# RF_Amplifier.net
KiCad netlist of a schematic drawn in Altium Designer
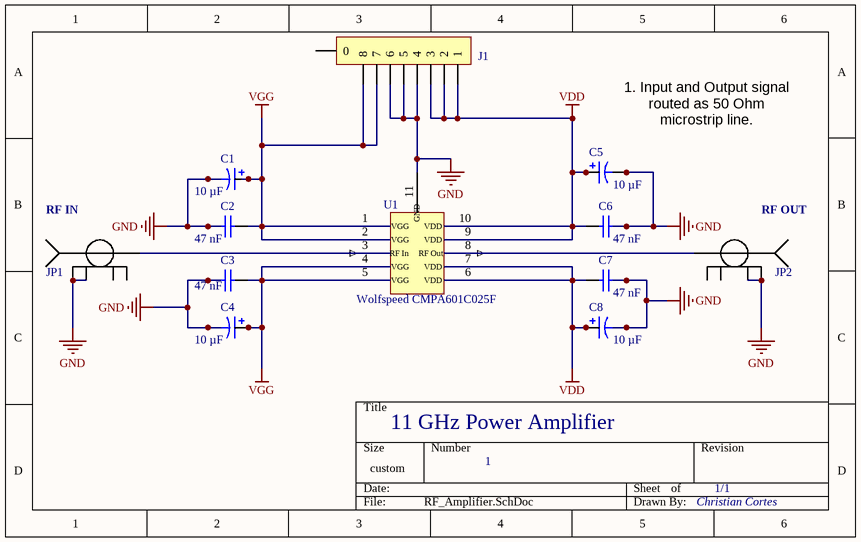
[diagram p0: RF_Amplifier.SchDoc]

(export (version "E")
  (design (tool "Eeschema 10.0.6"))
  (components
    (comp (ref "C1")
      (value "Panasonic 10SVP10M")
      (footprint "PCB-11675369-2")
      (description "CAP ALUM 10UF 10V 20% SMD")
      (fields (field (name "CAPACITANCE") "10 µF") (field (name "MANUFACTURER PART NUMBER") "10SVP10M"))
      (libsource (lib "") (part "SYM-11675369-1_1"))
    )
    (comp (ref "C2")
      (value "AVX Interconnect / Elco 12061C473KAT2A")
      (footprint "CAPC3216X94X50ML20T25")
      (description "CAP CER 0.047UF 100V X7R 1206")
      (fields (field (name "CAPACITANCE") "47 nF") (field (name "MANUFACTURER PART NUMBER") "12061C473KAT2A"))
      (libsource (lib "My Personal Space") (part "CAP-2"))
    )
    (comp (ref "C3")
      (value "AVX Interconnect / Elco 12061C473KAT2A")
      (footprint "CAPC3216X94X50ML20T25")
      (description "CAP CER 0.047UF 100V X7R 1206")
      (fields (field (name "CAPACITANCE") "47 nF") (field (name "MANUFACTURER PART NUMBER") "12061C473KAT2A"))
      (libsource (lib "My Personal Space") (part "CAP-2"))
    )
    (comp (ref "C4")
      (value "Panasonic 10SVP10M")
      (footprint "PCB-11675369-2")
      (description "CAP ALUM 10UF 10V 20% SMD")
      (fields (field (name "CAPACITANCE") "10 µF") (field (name "MANUFACTURER PART NUMBER") "10SVP10M"))
      (libsource (lib "") (part "SYM-11675369-1_1"))
    )
    (comp (ref "C5")
      (value "Panasonic 10SVP10M")
      (footprint "PCB-11675369-2")
      (description "CAP ALUM 10UF 10V 20% SMD")
      (fields (field (name "CAPACITANCE") "10 µF") (field (name "MANUFACTURER PART NUMBER") "10SVP10M"))
      (libsource (lib "My Personal Space") (part "SYM-11675369-1"))
    )
    (comp (ref "C6")
      (value "AVX Interconnect / Elco 12061C473KAT2A")
      (footprint "CAPC3216X94X50ML20T25")
      (description "CAP CER 0.047UF 100V X7R 1206")
      (fields (field (name "CAPACITANCE") "47 nF") (field (name "MANUFACTURER PART NUMBER") "12061C473KAT2A"))
      (libsource (lib "My Personal Space") (part "CAP-2"))
    )
    (comp (ref "C7")
      (value "AVX Interconnect / Elco 12061C473KAT2A")
      (footprint "CAPC3216X94X50ML20T25")
      (description "CAP CER 0.047UF 100V X7R 1206")
      (fields (field (name "CAPACITANCE") "47 nF") (field (name "MANUFACTURER PART NUMBER") "12061C473KAT2A"))
      (libsource (lib "My Personal Space") (part "CAP-2"))
    )
    (comp (ref "C8")
      (value "Panasonic 10SVP10M")
      (footprint "PCB-11675369-2")
      (description "CAP ALUM 10UF 10V 20% SMD")
      (fields (field (name "CAPACITANCE") "10 µF") (field (name "MANUFACTURER PART NUMBER") "10SVP10M"))
      (libsource (lib "My Personal Space") (part "SYM-11675369-1"))
    )
    (comp (ref "J1")
      (value "Molex 53398-0871")
      (footprint "PCB-330964-1")
      (description "Headers & Wire Housings VERTICAL HDR SMT 8P")
      (fields (field (name "MANUFACTURER PART NUMBER") "53398-0871"))
      (libsource (lib "My Personal Space") (part "SYM-330964-1"))
    )
    (comp (ref "JP1")
      (value "Molex 73251-2120")
      (footprint "PCB-gjx2rcg91tbhfhdn1i9r-1")
      (description "Rf Coax Conn, Sma, Jack, 50 Ohm, Pcb")
      (fields (field (name "MANUFACTURER PART NUMBER") "73251-2120"))
      (libsource (lib "My Personal Space") (part "SYM-4dee84f7198e9229-1"))
    )
    (comp (ref "JP2")
      (value "Molex 73251-2120")
      (footprint "PCB-gjx2rcg91tbhfhdn1i9r-1")
      (description "Rf Coax Conn, Sma, Jack, 50 Ohm, Pcb")
      (fields (field (name "MANUFACTURER PART NUMBER") "73251-2120"))
      (libsource (lib "My Personal Space") (part "SYM-4dee84f7198e9229-1"))
    )
    (comp (ref "U1")
      (value "Wolfspeed CMPA601C025F")
      (footprint "Wolfspeed CMPA601C025F-Footprint-1")
      (description "RF Amp Module Single Power Amp 12GHz 28V 11-Pin Case 440213")
      (fields (field (name "MANUFACTURER PART NUMBER") "CMPA601C025F - mod"))
      (libsource (lib "My Personal Space") (part "Wolfspeed CMPA601C025F-Symbol-1"))
    )
  )
  (nets
    (net (code "1") (name "GND") (class "Default")
      (node (ref "C1") (pin "2") (pinfunction "2_2") (pintype "passive"))
      (node (ref "C2") (pin "1") (pinfunction "1_1") (pintype "passive"))
      (node (ref "C3") (pin "1") (pinfunction "1_1") (pintype "passive"))
      (node (ref "C4") (pin "2") (pinfunction "2_2") (pintype "passive"))
      (node (ref "C5") (pin "2") (pinfunction "2_2") (pintype "passive"))
      (node (ref "C6") (pin "2") (pinfunction "2_2") (pintype "passive"))
      (node (ref "C7") (pin "2") (pinfunction "2_2") (pintype "passive"))
      (node (ref "C8") (pin "2") (pinfunction "2_2") (pintype "passive"))
      (node (ref "J1") (pin "4") (pinfunction "4_4") (pintype "passive"))
      (node (ref "J1") (pin "5") (pinfunction "5_5") (pintype "passive"))
      (node (ref "J1") (pin "6") (pinfunction "6_6") (pintype "passive"))
      (node (ref "JP1") (pin "2") (pinfunction "gnd_2") (pintype "passive"))
      (node (ref "JP1") (pin "3") (pinfunction "gnd_3") (pintype "passive"))
      (node (ref "JP2") (pin "2") (pinfunction "gnd_2") (pintype "passive"))
      (node (ref "JP2") (pin "3") (pinfunction "gnd_3") (pintype "passive"))
    )
    (net (code "2") (name "Net-(JP1-rf)") (class "Default")
      (node (ref "JP1") (pin "1") (pinfunction "rf_1") (pintype "passive"))
      (node (ref "U1") (pin "3") (pinfunction "RF_In_3") (pintype "output"))
    )
    (net (code "3") (name "Net-(JP2-rf)") (class "Default")
      (node (ref "JP2") (pin "1") (pinfunction "rf_1") (pintype "passive"))
      (node (ref "U1") (pin "8") (pinfunction "RF_Out_8") (pintype "input"))
    )
    (net (code "4") (name "VDD") (class "Default")
      (node (ref "C5") (pin "1") (pinfunction "1_1") (pintype "passive"))
      (node (ref "C6") (pin "1") (pinfunction "1_1") (pintype "passive"))
      (node (ref "C7") (pin "1") (pinfunction "1_1") (pintype "passive"))
      (node (ref "C8") (pin "1") (pinfunction "1_1") (pintype "passive"))
      (node (ref "J1") (pin "1") (pinfunction "1_1") (pintype "passive"))
      (node (ref "J1") (pin "2") (pinfunction "2_2") (pintype "passive"))
      (node (ref "J1") (pin "3") (pinfunction "3_3") (pintype "passive"))
      (node (ref "U1") (pin "10") (pinfunction "VDD_10") (pintype "passive"))
      (node (ref "U1") (pin "6") (pinfunction "VDD_6") (pintype "passive"))
      (node (ref "U1") (pin "7") (pinfunction "VDD_7") (pintype "passive"))
      (node (ref "U1") (pin "9") (pinfunction "VDD_9") (pintype "passive"))
    )
    (net (code "5") (name "VGG") (class "Default")
      (node (ref "C1") (pin "1") (pinfunction "1_1") (pintype "passive"))
      (node (ref "C2") (pin "2") (pinfunction "2_2") (pintype "passive"))
      (node (ref "C3") (pin "2") (pinfunction "2_2") (pintype "passive"))
      (node (ref "C4") (pin "1") (pinfunction "1_1") (pintype "passive"))
      (node (ref "J1") (pin "7") (pinfunction "7_7") (pintype "passive"))
      (node (ref "J1") (pin "8") (pinfunction "8_8") (pintype "passive"))
      (node (ref "U1") (pin "1") (pinfunction "VGG_1") (pintype "passive"))
      (node (ref "U1") (pin "2") (pinfunction "VGG_2") (pintype "passive"))
      (node (ref "U1") (pin "4") (pinfunction "VGG_4") (pintype "passive"))
      (node (ref "U1") (pin "5") (pinfunction "VGG_5") (pintype "passive"))
    )
    (net (code "6") (name "unconnected-(J1-Pad0)") (class "Default")
      (node (ref "J1") (pin "0") (pinfunction "0_0") (pintype "passive"))
    )
    (net (code "7") (name "unconnected-(JP1-gnd-Pad4)") (class "Default")
      (node (ref "JP1") (pin "4") (pinfunction "gnd_4") (pintype "passive"))
    )
    (net (code "8") (name "unconnected-(JP1-gnd-Pad5)") (class "Default")
      (node (ref "JP1") (pin "5") (pinfunction "gnd_5") (pintype "passive"))
    )
    (net (code "9") (name "unconnected-(JP2-gnd-Pad4)") (class "Default")
      (node (ref "JP2") (pin "4") (pinfunction "gnd_4") (pintype "passive"))
    )
    (net (code "10") (name "unconnected-(JP2-gnd-Pad5)") (class "Default")
      (node (ref "JP2") (pin "5") (pinfunction "gnd_5") (pintype "passive"))
    )
    (net (code "11") (name "unconnected-(U1-GND-Pad11)") (class "Default")
      (node (ref "U1") (pin "11") (pinfunction "GND_11") (pintype "passive"))
    )
  )
)
